# Main.net
KiCad netlist of a schematic drawn in Altium Designer
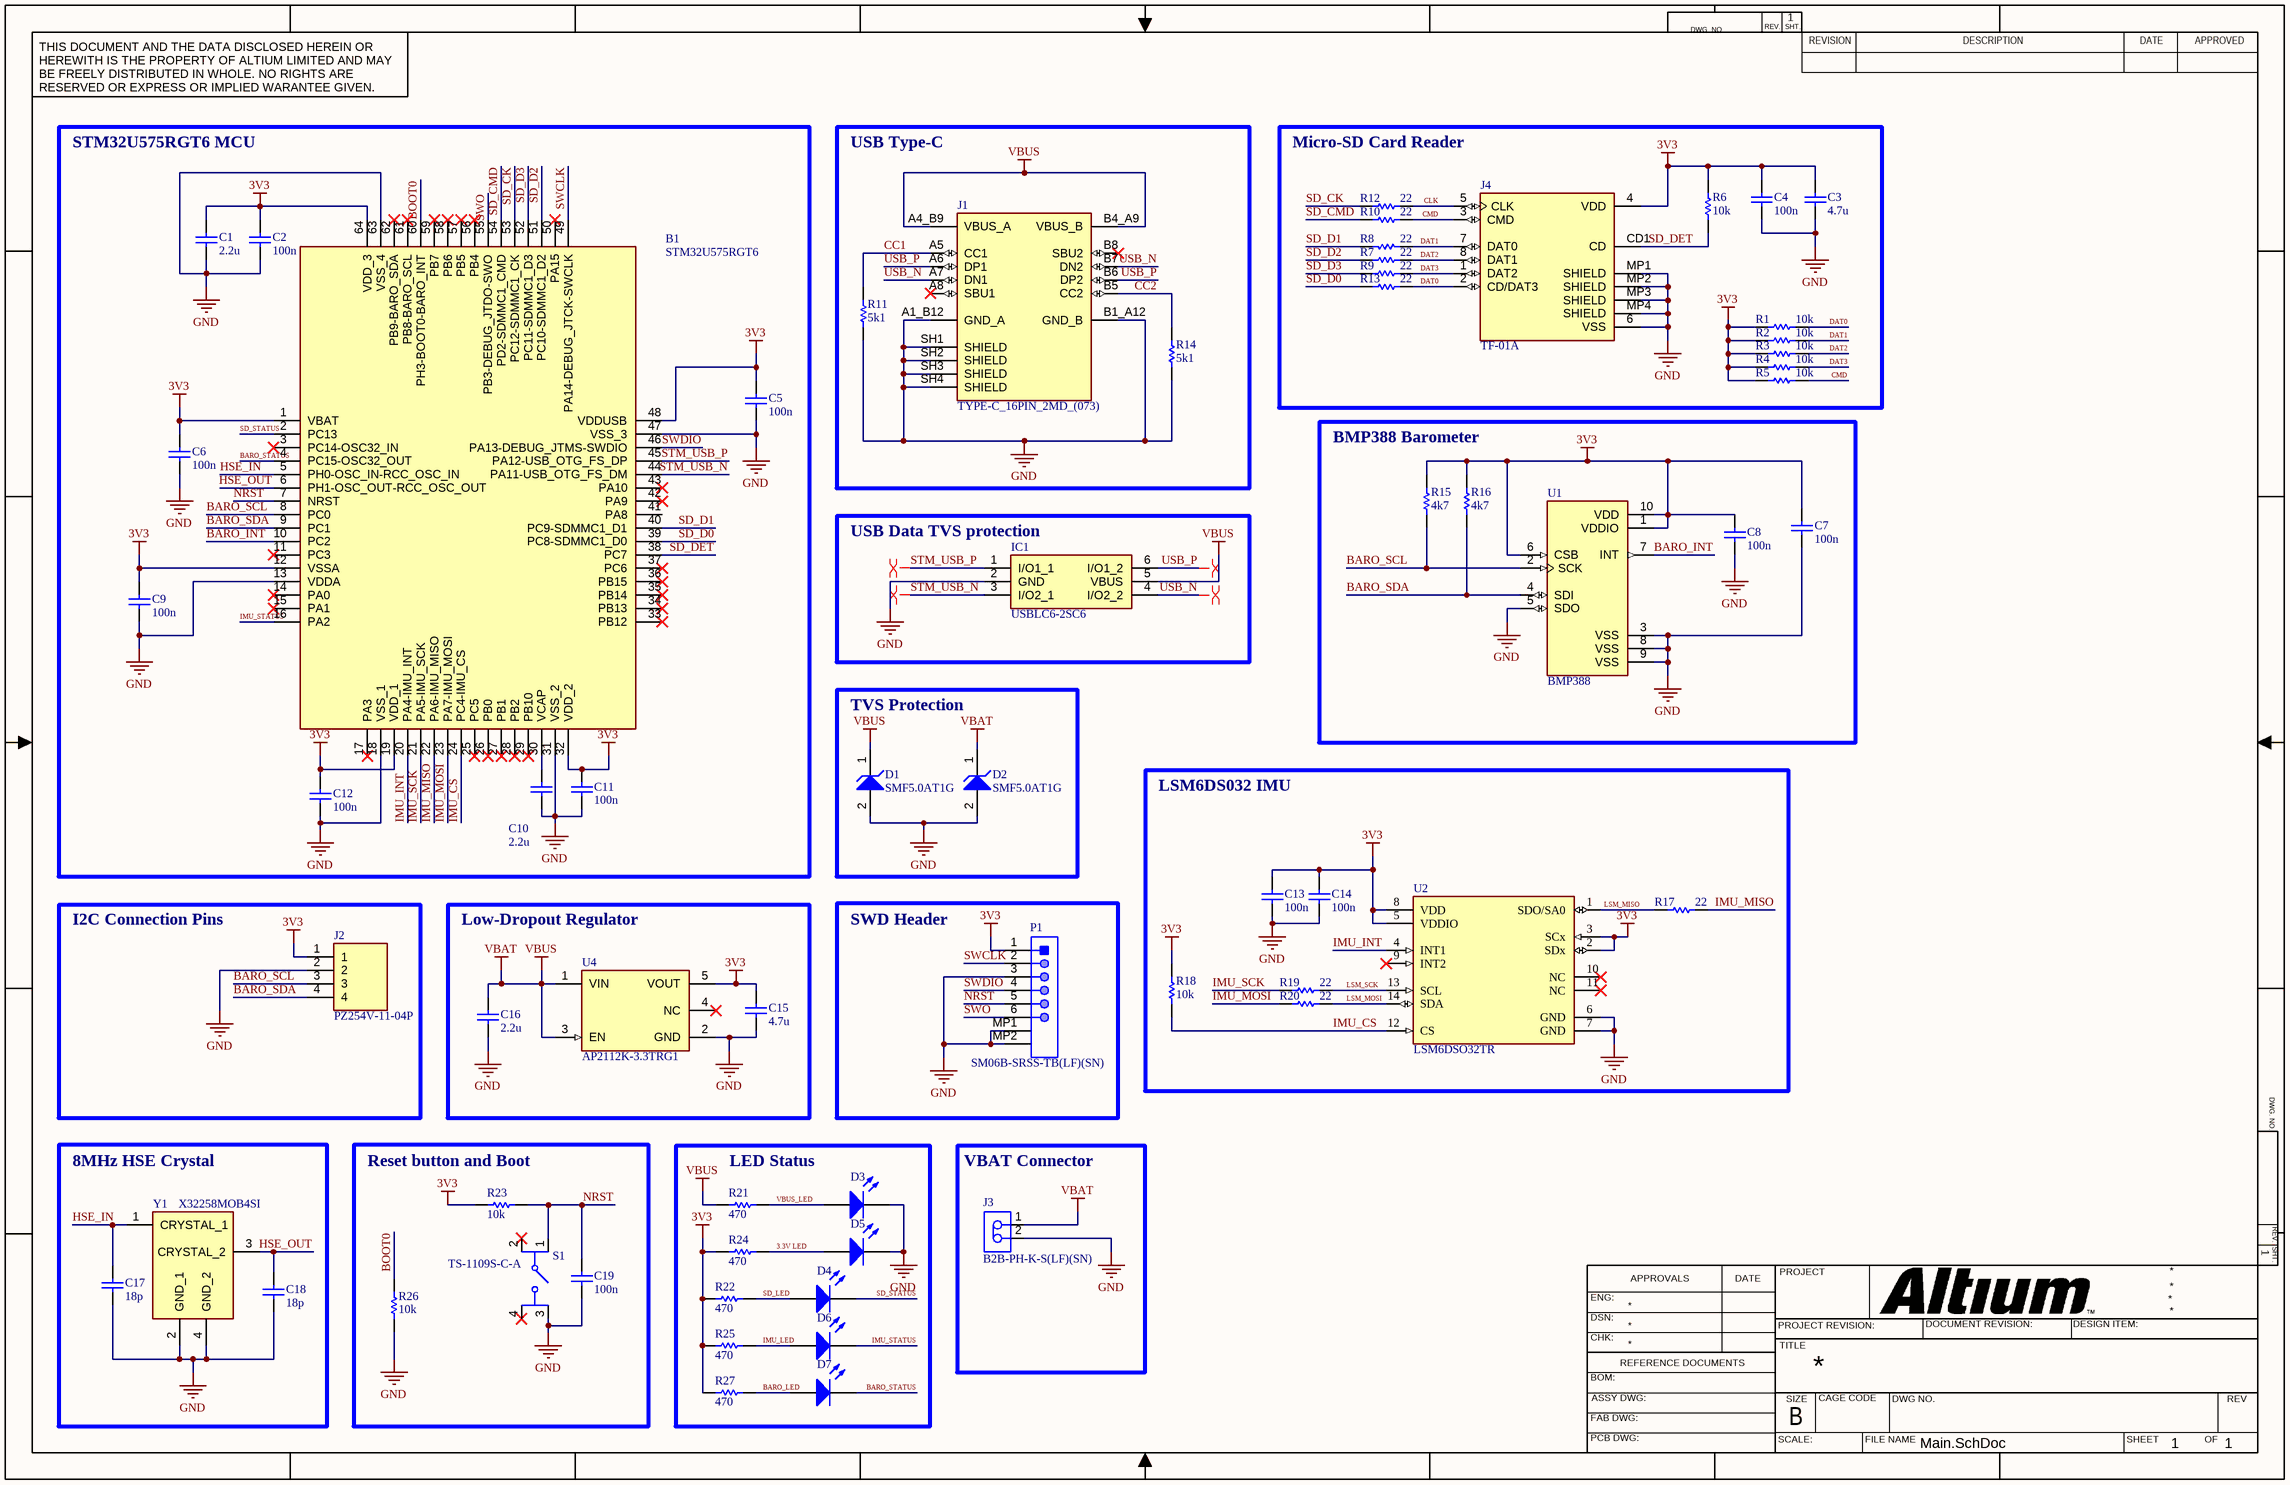
[diagram p0: Main.SchDoc]

(export (version "E")
  (design (tool "Eeschema 10.0.6"))
  (components
    (comp (ref "B1")
      (value "STM32U575RGT6")
      (footprint "SamacSys:QFP50P1200X1200X160-64N")
      (libsource (lib "SamacSys") (part "STM32U575RGT6"))
    )
    (comp (ref "C1")
      (value "2.2u")
      (footprint "CAPC1608X90X40LL10T20")
      (description "2.2u Capacitor 0603 CL10A225KO8NNNC")
      (fields (field (name "Comment") "Capacitor"))
      (libsource (lib "Simulation Generic Components") (part "Capacitor"))
    )
    (comp (ref "C2")
      (value "100n")
      (footprint "CAPC0402(1005)60_L")
      (description "100n Capacitor 0402 CL05B104KO5NNNC")
      (fields (field (name "Comment") "Capacitor"))
      (libsource (lib "Simulation Generic Components") (part "Capacitor"))
    )
    (comp (ref "C3")
      (value "4.7u")
      (footprint "CAPC1608X90X40LL10T20")
      (description "4.7u Capacitor 0603 CL10A475KO8NNNC")
      (fields (field (name "Comment") "Capacitor"))
      (libsource (lib "Simulation Generic Components") (part "Capacitor"))
    )
    (comp (ref "C4")
      (value "100n")
      (footprint "CAPC0402(1005)60_L")
      (description "100n Capacitor 0402 CL05B104KO5NNNC")
      (fields (field (name "Comment") "Capacitor"))
      (libsource (lib "Simulation Generic Components") (part "Capacitor"))
    )
    (comp (ref "C5")
      (value "100n")
      (footprint "CAPC0402(1005)60_L")
      (description "100n Capacitor 0402 CL05B104KO5NNNC")
      (fields (field (name "Comment") "Capacitor"))
      (libsource (lib "Simulation Generic Components") (part "Capacitor"))
    )
    (comp (ref "C6")
      (value "100n")
      (footprint "CAPC0402(1005)60_L")
      (description "100n Capacitor 0402 CL05B104KO5NNNC")
      (fields (field (name "Comment") "Capacitor"))
      (libsource (lib "Simulation Generic Components") (part "Capacitor"))
    )
    (comp (ref "C7")
      (value "100n")
      (footprint "CAPC0402(1005)60_L")
      (description "100n Capacitor 0402 CL05B104KO5NNNC")
      (fields (field (name "Comment") "Capacitor"))
      (libsource (lib "Simulation Generic Components") (part "Capacitor"))
    )
    (comp (ref "C8")
      (value "100n")
      (footprint "CAPC0402(1005)60_L")
      (description "100n Capacitor 0402 CL05B104KO5NNNC")
      (fields (field (name "Comment") "Capacitor"))
      (libsource (lib "Simulation Generic Components") (part "Capacitor"))
    )
    (comp (ref "C9")
      (value "100n")
      (footprint "CAPC0402(1005)60_L")
      (description "100n Capacitor 0402 CL05B104KO5NNNC")
      (fields (field (name "Comment") "Capacitor"))
      (libsource (lib "Simulation Generic Components") (part "Capacitor"))
    )
    (comp (ref "C10")
      (value "2.2u")
      (footprint "CAPC1608X90X40LL10T20")
      (description "2.2u Capacitor 0603 CL10A225KO8NNNC")
      (fields (field (name "Comment") "Capacitor"))
      (libsource (lib "Simulation Generic Components") (part "Capacitor"))
    )
    (comp (ref "C11")
      (value "100n")
      (footprint "CAPC0402(1005)60_L")
      (description "100n Capacitor 0402 CL05B104KO5NNNC")
      (fields (field (name "Comment") "Capacitor"))
      (libsource (lib "Simulation Generic Components") (part "Capacitor"))
    )
    (comp (ref "C12")
      (value "100n")
      (footprint "CAPC0402(1005)60_L")
      (description "100n Capacitor 0402 CL05B104KO5NNNC")
      (fields (field (name "Comment") "Capacitor"))
      (libsource (lib "Simulation Generic Components") (part "Capacitor"))
    )
    (comp (ref "C13")
      (value "100n")
      (footprint "CAPC0402(1005)60_L")
      (description "100n Capacitor 0402 CL05B104KO5NNNC")
      (fields (field (name "Comment") "Capacitor"))
      (libsource (lib "Simulation Generic Components") (part "Capacitor"))
    )
    (comp (ref "C14")
      (value "100n")
      (footprint "CAPC0402(1005)60_L")
      (description "100n Capacitor 0402 CL05B104KO5NNNC")
      (fields (field (name "Comment") "Capacitor"))
      (libsource (lib "Simulation Generic Components") (part "Capacitor"))
    )
    (comp (ref "C15")
      (value "4.7u")
      (footprint "CAPC1608X90X40LL10T20")
      (description "4.7u Capacitor 0603 CL10A475KO8NNNC")
      (fields (field (name "Comment") "Capacitor"))
      (libsource (lib "Simulation Generic Components") (part "Capacitor"))
    )
    (comp (ref "C16")
      (value "2.2u")
      (footprint "CAPC1608X90X40LL10T20")
      (description "2.2u Capacitor 0603 CL10A225KO8NNNC")
      (fields (field (name "Comment") "Capacitor"))
      (libsource (lib "Simulation Generic Components") (part "Capacitor"))
    )
    (comp (ref "C17")
      (value "18p")
      (footprint "CAPC0402(1005)60_L")
      (description "18p Capacitor 0402 0402CG180J500NT")
      (fields (field (name "Comment") "Capacitor"))
      (libsource (lib "Simulation Generic Components") (part "Capacitor"))
    )
    (comp (ref "C18")
      (value "18p")
      (footprint "CAPC0402(1005)60_L")
      (description "18p Capacitor 0402 0402CG180J500NT")
      (fields (field (name "Comment") "Capacitor"))
      (libsource (lib "Simulation Generic Components") (part "Capacitor"))
    )
    (comp (ref "C19")
      (value "100n")
      (footprint "CAPC0402(1005)60_L")
      (description "100n Capacitor 0402 CL05B104KO5NNNC")
      (fields (field (name "Comment") "Capacitor"))
      (libsource (lib "Simulation Generic Components") (part "Capacitor"))
    )
    (comp (ref "D1")
      (value "SMF5.0AT1G")
      (footprint "ONSC-SOD-123FL-2-498_V")
      (description "200 W Transient Voltage Suppressor, 2-Pin SOD-123FL, Pb-Free, Tape and Reel")
      (fields (field (name "MANUFACTURER") "On Semiconductor"))
      (libsource (lib "Altium Content Vault") (part "ONSC-K1A2-2"))
    )
    (comp (ref "D2")
      (value "SMF5.0AT1G")
      (footprint "ONSC-SOD-123FL-2-498_V")
      (description "200 W Transient Voltage Suppressor, 2-Pin SOD-123FL, Pb-Free, Tape and Reel")
      (fields (field (name "MANUFACTURER") "On Semiconductor"))
      (libsource (lib "Altium Content Vault") (part "ONSC-K1A2-2"))
    )
    (comp (ref "D3")
      (value "Light-Emitting Diode")
      (footprint "D0603:LTST-C191KRKT_V")
      (description "Red Light-Emitting Diode 0603 KT-0603R")
      (libsource (lib "Simulation Generic Components") (part "LED"))
    )
    (comp (ref "D4")
      (value "Light-Emitting Diode")
      (footprint "D0603:LTST-C191KRKT_V")
      (description "Red Light-Emitting Diode 0603 KT-0603R")
      (libsource (lib "Simulation Generic Components") (part "LED"))
    )
    (comp (ref "D5")
      (value "Light-Emitting Diode")
      (footprint "D0603:LTST-C191KRKT_V")
      (description "Red Light-Emitting Diode 0603 KT-0603R")
      (libsource (lib "Simulation Generic Components") (part "LED"))
    )
    (comp (ref "D6")
      (value "Light-Emitting Diode")
      (footprint "D0603:LTST-C191KRKT_V")
      (description "Red Light-Emitting Diode 0603 KT-0603R")
      (libsource (lib "Simulation Generic Components") (part "LED"))
    )
    (comp (ref "D7")
      (value "Light-Emitting Diode")
      (footprint "D0603:LTST-C191KRKT_V")
      (description "Red Light-Emitting Diode 0603 KT-0603R")
      (libsource (lib "Simulation Generic Components") (part "LED"))
    )
    (comp (ref "IC1")
      (value "USBLC6-2SC6")
      (footprint "SamacSys:SOT95P280X145-6N")
      (description "Integrated Circuit")
      (fields (field (name "MOUSER PART NUMBER") "511-USBLC6-2SC6"))
      (libsource (lib "SamacSys") (part "USBLC6-2SC6"))
    )
    (comp (ref "J1")
      (value "TYPE-C_16PIN_2MD_(073)")
      (footprint "SHOUHAN_TYPE-C_16PIN_2MD_(073)")
      (description "DC-5V 5A Type C USB")
      (fields (field (name "MP") "TYPE-C 16PIN 2MD (073)") (field (name "MF") "Shouhan"))
      (libsource (lib "Barney's Workspace") (part "TYPE-C_16PIN_2MD_(073)"))
    )
    (comp (ref "J2")
      (value "PZ254V-11-04P")
      (footprint "SamacSys:HDRV4W64P0X254_1X4_1016X250X890P")
      (description "Connector")
      (libsource (lib "SamacSys") (part "PZ254V-11-04P"))
    )
    (comp (ref "J3")
      (value "B2B-PH-K-S(LF)(SN)")
      (footprint "JST-B2B-PH-K-S_V")
      (fields (field (name "MANUFACTURER") "JST"))
      (libsource (lib "Altium Content Vault") (part "CN-2P-F-QF2"))
    )
    (comp (ref "J4")
      (value "TF-01A")
      (footprint "TF-01A")
      (description "Standard Card Edge Connectors")
      (fields (field (name "MF") "HRO Electronics Co., Ltd."))
      (libsource (lib "Barney's Workspace") (part "TF-01A"))
    )
    (comp (ref "P1")
      (value "SM06B-SRSS-TB(LF)(SN)")
      (footprint "JST-SM06B-SRSS-TB_V")
      (description "Male Header, Pitch 1 mm, 1 x 6 Position, Height 2.95 mm, -25 to 85 degC, RoHS, Tape and Reel")
      (fields (field (name "MANUFACTURER") "JST"))
      (libsource (lib "Altium Content Vault") (part "CN-1P-2M-R6"))
    )
    (comp (ref "R1")
      (value "10k")
      (footprint "RESC0402(1005)_L")
      (description "10k Resistor 0402 0402WGF1002TCE")
      (fields (field (name "Comment") "Resistor"))
      (libsource (lib "Simulation Generic Components") (part "Resistor"))
    )
    (comp (ref "R2")
      (value "10k")
      (footprint "RESC0402(1005)_L")
      (description "10k Resistor 0402 0402WGF1002TCE")
      (fields (field (name "Comment") "Resistor"))
      (libsource (lib "Simulation Generic Components") (part "Resistor"))
    )
    (comp (ref "R3")
      (value "10k")
      (footprint "RESC0402(1005)_L")
      (description "10k Resistor 0402 0402WGF1002TCE")
      (fields (field (name "Comment") "Resistor"))
      (libsource (lib "Simulation Generic Components") (part "Resistor"))
    )
    (comp (ref "R4")
      (value "10k")
      (footprint "RESC0402(1005)_L")
      (description "10k Resistor 0402 0402WGF1002TCE")
      (fields (field (name "Comment") "Resistor"))
      (libsource (lib "Simulation Generic Components") (part "Resistor"))
    )
    (comp (ref "R5")
      (value "10k")
      (footprint "RESC0402(1005)_L")
      (description "10k Resistor 0402 0402WGF1002TCE")
      (fields (field (name "Comment") "Resistor"))
      (libsource (lib "Simulation Generic Components") (part "Resistor"))
    )
    (comp (ref "R6")
      (value "10k")
      (footprint "RESC0402(1005)_L")
      (description "10k Resistor 0402 0402WGF1002TCE")
      (fields (field (name "Comment") "Resistor"))
      (libsource (lib "Simulation Generic Components") (part "Resistor"))
    )
    (comp (ref "R7")
      (value "22")
      (footprint "RESC0402(1005)_L")
      (description "22 Resistor 0402 0402WGF220JTCE")
      (fields (field (name "Comment") "Resistor"))
      (libsource (lib "Simulation Generic Components") (part "Resistor"))
    )
    (comp (ref "R8")
      (value "22")
      (footprint "RESC0402(1005)_L")
      (description "22 Resistor 0402 0402WGF220JTCE")
      (fields (field (name "Comment") "Resistor"))
      (libsource (lib "Simulation Generic Components") (part "Resistor"))
    )
    (comp (ref "R9")
      (value "22")
      (footprint "RESC0402(1005)_L")
      (description "22 Resistor 0402 0402WGF220JTCE")
      (fields (field (name "Comment") "Resistor"))
      (libsource (lib "Simulation Generic Components") (part "Resistor"))
    )
    (comp (ref "R10")
      (value "22")
      (footprint "RESC0402(1005)_L")
      (description "22 Resistor 0402 0402WGF220JTCE")
      (fields (field (name "Comment") "Resistor"))
      (libsource (lib "Simulation Generic Components") (part "Resistor"))
    )
    (comp (ref "R11")
      (value "5k1")
      (footprint "RESC0402(1005)_L")
      (description "5k1 Resistor 0402 0402WGF5101TCE")
      (fields (field (name "Comment") "Resistor"))
      (libsource (lib "Simulation Generic Components") (part "Resistor"))
    )
    (comp (ref "R12")
      (value "22")
      (footprint "RESC0402(1005)_L")
      (description "22 Resistor 0402 0402WGF220JTCE")
      (fields (field (name "Comment") "Resistor"))
      (libsource (lib "Simulation Generic Components") (part "Resistor"))
    )
    (comp (ref "R13")
      (value "22")
      (footprint "RESC0402(1005)_L")
      (description "22 Resistor 0402 0402WGF220JTCE")
      (fields (field (name "Comment") "Resistor"))
      (libsource (lib "Simulation Generic Components") (part "Resistor"))
    )
    (comp (ref "R14")
      (value "5k1")
      (footprint "RESC0402(1005)_L")
      (description "5k1 Resistor 0402 0402WGF5101TCE")
      (fields (field (name "Comment") "Resistor"))
      (libsource (lib "Simulation Generic Components") (part "Resistor"))
    )
    (comp (ref "R15")
      (value "4k7")
      (footprint "RESC0402(1005)_L")
      (description "4k7 Resistor 0402 0402WGF4701TCE")
      (fields (field (name "Comment") "Resistor"))
      (libsource (lib "Simulation Generic Components") (part "Resistor"))
    )
    (comp (ref "R16")
      (value "4k7")
      (footprint "RESC0402(1005)_L")
      (description "4k7 Resistor 0402 0402WGF4701TCE")
      (fields (field (name "Comment") "Resistor"))
      (libsource (lib "Simulation Generic Components") (part "Resistor"))
    )
    (comp (ref "R17")
      (value "22")
      (footprint "RESC0402(1005)_L")
      (description "22 Resistor 0402 0402WGF220JTCE")
      (fields (field (name "Comment") "Resistor"))
      (libsource (lib "Simulation Generic Components") (part "Resistor"))
    )
    (comp (ref "R18")
      (value "10k")
      (footprint "RESC0402(1005)_L")
      (description "10k Resistor 0402 0402WGF1002TCE")
      (fields (field (name "Comment") "Resistor"))
      (libsource (lib "Simulation Generic Components") (part "Resistor"))
    )
    (comp (ref "R19")
      (value "22")
      (footprint "RESC0402(1005)_L")
      (description "22 Resistor 0402 0402WGF220JTCE")
      (fields (field (name "Comment") "Resistor"))
      (libsource (lib "Simulation Generic Components") (part "Resistor"))
    )
    (comp (ref "R20")
      (value "22")
      (footprint "RESC0402(1005)_L")
      (description "22 Resistor 0402 0402WGF220JTCE")
      (fields (field (name "Comment") "Resistor"))
      (libsource (lib "Simulation Generic Components") (part "Resistor"))
    )
    (comp (ref "R21")
      (value "470")
      (footprint "R0603:RESC1608X55X25LL10T15")
      (description "470 Resistor 0603 0603WAF4700T5E")
      (fields (field (name "Comment") "Resistor"))
      (libsource (lib "Simulation Generic Components") (part "Resistor"))
    )
    (comp (ref "R22")
      (value "470")
      (footprint "R0603:RESC1608X55X25LL10T15")
      (description "470 Resistor 0603 0603WAF4700T5E")
      (fields (field (name "Comment") "Resistor"))
      (libsource (lib "Simulation Generic Components") (part "Resistor"))
    )
    (comp (ref "R23")
      (value "10k")
      (footprint "RESC0402(1005)_L")
      (description "10k Resistor 0402 0402WGF1002TCE")
      (fields (field (name "Comment") "Resistor"))
      (libsource (lib "Simulation Generic Components") (part "Resistor"))
    )
    (comp (ref "R24")
      (value "470")
      (footprint "R0603:RESC1608X55X25LL10T15")
      (description "470 Resistor 0603 0603WAF4700T5E")
      (fields (field (name "Comment") "Resistor"))
      (libsource (lib "Simulation Generic Components") (part "Resistor"))
    )
    (comp (ref "R25")
      (value "470")
      (footprint "R0603:RESC1608X55X25LL10T15")
      (description "470 Resistor 0603 0603WAF4700T5E")
      (fields (field (name "Comment") "Resistor"))
      (libsource (lib "Simulation Generic Components") (part "Resistor"))
    )
    (comp (ref "R26")
      (value "10k")
      (footprint "RESC0402(1005)_L")
      (description "10k Resistor 0402 0402WGF1002TCE")
      (fields (field (name "Comment") "Resistor"))
      (libsource (lib "Simulation Generic Components") (part "Resistor"))
    )
    (comp (ref "R27")
      (value "470")
      (footprint "R0603:RESC1608X55X25LL10T15")
      (description "470 Resistor 0603 0603WAF4700T5E")
      (fields (field (name "Comment") "Resistor"))
      (libsource (lib "Simulation Generic Components") (part "Resistor"))
    )
    (comp (ref "S1")
      (value "TS-1109S-C-A")
      (footprint "SamacSys:TS1109SCA")
      (description "Switch (4-Pin Push)")
      (libsource (lib "*") (part "TS-1109S-C-A"))
    )
    (comp (ref "U1")
      (value "BMP388")
      (footprint "PQFN50P200X200X80-10N")
      (description "P-Sensor SPI I2C 1, 25 Bar SMD")
      (libsource (lib "Barney's Workspace") (part "BMP388"))
    )
    (comp (ref "U2")
      (value "LSM6DSO32TR")
      (footprint "FP-LGA-14L-DM00249496-MFG")
      (description "INEMO INERTIAL MODULE: 3D ACCELE")
      (libsource (lib "Altium Content Vault") (part "593856c316c551aebc7657d93cdb4f0"))
    )
    (comp (ref "U4")
      (value "AP2112K-3.3TRG1")
      (footprint "FP-SOT25-IPC_C")
      (description "IC REG LINEAR 3.3V 600MA SOT25")
      (libsource (lib "Altium Content Vault") (part "c8ab751aee5229183125ab046a11caa"))
    )
    (comp (ref "Y1")
      (value "X32258MOB4SI")
      (footprint "SamacSys:X32258MOB4SI")
      (description "Crystal or Oscillator")
      (libsource (lib "SamacSys") (part "X32258MOB4SI"))
    )
  )
  (nets
    (net (code "1") (name "/3.3V LED") (class "Default")
      (node (ref "D5") (pin "1") (pinfunction "A_1") (pintype "passive"))
      (node (ref "R24") (pin "2") (pinfunction "2_2") (pintype "passive"))
    )
    (net (code "2") (name "/BARO_INT") (class "Default")
      (node (ref "B1") (pin "10") (pinfunction "PC2_10") (pintype "passive"))
      (node (ref "U1") (pin "7") (pinfunction "INT_7") (pintype "output"))
    )
    (net (code "3") (name "/BARO_LED") (class "Default")
      (node (ref "D7") (pin "1") (pinfunction "A_1") (pintype "passive"))
      (node (ref "R27") (pin "2") (pinfunction "2_2") (pintype "passive"))
    )
    (net (code "4") (name "/BARO_SCL") (class "Default")
      (node (ref "B1") (pin "8") (pinfunction "PC0_8") (pintype "passive"))
      (node (ref "J2") (pin "3") (pinfunction "3_3") (pintype "passive"))
      (node (ref "R15") (pin "1") (pinfunction "1_1") (pintype "passive"))
      (node (ref "U1") (pin "2") (pinfunction "SCK_2") (pintype "input"))
    )
    (net (code "5") (name "/BARO_SDA") (class "Default")
      (node (ref "B1") (pin "9") (pinfunction "PC1_9") (pintype "passive"))
      (node (ref "J2") (pin "4") (pinfunction "4_4") (pintype "passive"))
      (node (ref "R16") (pin "1") (pinfunction "1_1") (pintype "passive"))
      (node (ref "U1") (pin "4") (pinfunction "SDI_4") (pintype "bidirectional"))
    )
    (net (code "6") (name "/BARO_STATUS") (class "Default")
      (node (ref "B1") (pin "4") (pinfunction "PC15-OSC32_OUT_4") (pintype "passive"))
      (node (ref "D7") (pin "2") (pinfunction "K_2") (pintype "passive"))
    )
    (net (code "7") (name "/BOOT0") (class "Default")
      (node (ref "B1") (pin "60") (pinfunction "PH3-BOOT0-BARO_INT_60") (pintype "passive"))
      (node (ref "R26") (pin "2") (pinfunction "2_2") (pintype "passive"))
    )
    (net (code "8") (name "/CC1") (class "Default")
      (node (ref "J1") (pin "A5") (pinfunction "CC1_A5") (pintype "bidirectional"))
      (node (ref "R11") (pin "2") (pinfunction "2_2") (pintype "passive"))
    )
    (net (code "9") (name "/CC2") (class "Default")
      (node (ref "J1") (pin "B5") (pinfunction "CC2_B5") (pintype "bidirectional"))
      (node (ref "R14") (pin "2") (pinfunction "2_2") (pintype "passive"))
    )
    (net (code "10") (name "/CLK") (class "Default")
      (node (ref "J4") (pin "5") (pinfunction "CLK_5") (pintype "bidirectional"))
      (node (ref "R12") (pin "1") (pinfunction "1_1") (pintype "passive"))
    )
    (net (code "11") (name "/CMD") (class "Default")
      (node (ref "J4") (pin "3") (pinfunction "CMD_3") (pintype "bidirectional"))
      (node (ref "R10") (pin "1") (pinfunction "1_1") (pintype "passive"))
      (node (ref "R5") (pin "2") (pinfunction "2_2") (pintype "passive"))
    )
    (net (code "12") (name "/DAT0") (class "Default")
      (node (ref "J4") (pin "2") (pinfunction "CD/DAT3_2") (pintype "bidirectional"))
      (node (ref "R1") (pin "2") (pinfunction "2_2") (pintype "passive"))
      (node (ref "R13") (pin "1") (pinfunction "1_1") (pintype "passive"))
    )
    (net (code "13") (name "/DAT1") (class "Default")
      (node (ref "J4") (pin "7") (pinfunction "DAT0_7") (pintype "bidirectional"))
      (node (ref "R2") (pin "2") (pinfunction "2_2") (pintype "passive"))
      (node (ref "R8") (pin "2") (pinfunction "2_2") (pintype "passive"))
    )
    (net (code "14") (name "/DAT2") (class "Default")
      (node (ref "J4") (pin "8") (pinfunction "DAT1_8") (pintype "bidirectional"))
      (node (ref "R3") (pin "2") (pinfunction "2_2") (pintype "passive"))
      (node (ref "R7") (pin "1") (pinfunction "1_1") (pintype "passive"))
    )
    (net (code "15") (name "/DAT3") (class "Default")
      (node (ref "J4") (pin "1") (pinfunction "DAT2_1") (pintype "bidirectional"))
      (node (ref "R4") (pin "2") (pinfunction "2_2") (pintype "passive"))
      (node (ref "R9") (pin "1") (pinfunction "1_1") (pintype "passive"))
    )
    (net (code "16") (name "/HSE_IN") (class "Default")
      (node (ref "B1") (pin "5") (pinfunction "PH0-OSC_IN-RCC_OSC_IN_5") (pintype "passive"))
      (node (ref "C17") (pin "2") (pinfunction "2_2") (pintype "passive"))
      (node (ref "Y1") (pin "1") (pinfunction "CRYSTAL_1_1") (pintype "passive"))
    )
    (net (code "17") (name "/HSE_OUT") (class "Default")
      (node (ref "B1") (pin "6") (pinfunction "PH1-OSC_OUT-RCC_OSC_OUT_6") (pintype "passive"))
      (node (ref "C18") (pin "2") (pinfunction "2_2") (pintype "passive"))
      (node (ref "Y1") (pin "3") (pinfunction "CRYSTAL_2_3") (pintype "passive"))
    )
    (net (code "18") (name "/IMU_CS") (class "Default")
      (node (ref "B1") (pin "24") (pinfunction "PC4-IMU_CS_24") (pintype "passive"))
      (node (ref "R18") (pin "1") (pinfunction "1_1") (pintype "passive"))
      (node (ref "U2") (pin "12") (pinfunction "CS_12") (pintype "input"))
    )
    (net (code "19") (name "/IMU_INT") (class "Default")
      (node (ref "B1") (pin "20") (pinfunction "PA4-IMU_INT_20") (pintype "passive"))
      (node (ref "U2") (pin "4") (pinfunction "INT1_4") (pintype "input"))
    )
    (net (code "20") (name "/IMU_LED") (class "Default")
      (node (ref "D6") (pin "1") (pinfunction "A_1") (pintype "passive"))
      (node (ref "R25") (pin "2") (pinfunction "2_2") (pintype "passive"))
    )
    (net (code "21") (name "/IMU_MISO") (class "Default")
      (node (ref "B1") (pin "22") (pinfunction "PA6-IMU_MISO_22") (pintype "passive"))
      (node (ref "R17") (pin "1") (pinfunction "1_1") (pintype "passive"))
    )
    (net (code "22") (name "/IMU_MOSI") (class "Default")
      (node (ref "B1") (pin "23") (pinfunction "PA7-IMU_MOSI_23") (pintype "passive"))
      (node (ref "R20") (pin "2") (pinfunction "2_2") (pintype "passive"))
    )
    (net (code "23") (name "/IMU_SCK") (class "Default")
      (node (ref "B1") (pin "21") (pinfunction "PA5-IMU_SCK_21") (pintype "passive"))
      (node (ref "R19") (pin "2") (pinfunction "2_2") (pintype "passive"))
    )
    (net (code "24") (name "/IMU_STATUS") (class "Default")
      (node (ref "B1") (pin "16") (pinfunction "PA2_16") (pintype "passive"))
      (node (ref "D6") (pin "2") (pinfunction "K_2") (pintype "passive"))
    )
    (net (code "25") (name "/LSM_MISO") (class "Default")
      (node (ref "R17") (pin "2") (pinfunction "2_2") (pintype "passive"))
      (node (ref "U2") (pin "1") (pinfunction "SDO/SA0_1") (pintype "bidirectional"))
    )
    (net (code "26") (name "/LSM_MOSI") (class "Default")
      (node (ref "R20") (pin "1") (pinfunction "1_1") (pintype "passive"))
      (node (ref "U2") (pin "14") (pinfunction "SDA_14") (pintype "bidirectional"))
    )
    (net (code "27") (name "/LSM_SCK") (class "Default")
      (node (ref "R19") (pin "1") (pinfunction "1_1") (pintype "passive"))
      (node (ref "U2") (pin "13") (pinfunction "SCL_13") (pintype "input"))
    )
    (net (code "28") (name "/NRST") (class "Default")
      (node (ref "B1") (pin "7") (pinfunction "NRST_7") (pintype "passive"))
      (node (ref "C19") (pin "2") (pinfunction "2_2") (pintype "passive"))
      (node (ref "P1") (pin "5") (pinfunction "5_5") (pintype "passive"))
      (node (ref "R23") (pin "1") (pinfunction "1_1") (pintype "passive"))
      (node (ref "S1") (pin "1") (pinfunction "COM_1_1") (pintype "passive"))
    )
    (net (code "29") (name "/SD_CK") (class "Default")
      (node (ref "B1") (pin "53") (pinfunction "PC12-SDMMC1_CK_53") (pintype "passive"))
      (node (ref "R12") (pin "2") (pinfunction "2_2") (pintype "passive"))
    )
    (net (code "30") (name "/SD_CMD") (class "Default")
      (node (ref "B1") (pin "54") (pinfunction "PD2-SDMMC1_CMD_54") (pintype "passive"))
      (node (ref "R10") (pin "2") (pinfunction "2_2") (pintype "passive"))
    )
    (net (code "31") (name "/SD_D0") (class "Default")
      (node (ref "B1") (pin "39") (pinfunction "PC8-SDMMC1_D0_39") (pintype "passive"))
      (node (ref "R13") (pin "2") (pinfunction "2_2") (pintype "passive"))
    )
    (net (code "32") (name "/SD_D1") (class "Default")
      (node (ref "B1") (pin "40") (pinfunction "PC9-SDMMC1_D1_40") (pintype "passive"))
      (node (ref "R8") (pin "1") (pinfunction "1_1") (pintype "passive"))
    )
    (net (code "33") (name "/SD_D2") (class "Default")
      (node (ref "B1") (pin "51") (pinfunction "PC10-SDMMC1_D2_51") (pintype "passive"))
      (node (ref "R7") (pin "2") (pinfunction "2_2") (pintype "passive"))
    )
    (net (code "34") (name "/SD_D3") (class "Default")
      (node (ref "B1") (pin "52") (pinfunction "PC11-SDMMC1_D3_52") (pintype "passive"))
      (node (ref "R9") (pin "2") (pinfunction "2_2") (pintype "passive"))
    )
    (net (code "35") (name "/SD_DET") (class "Default")
      (node (ref "B1") (pin "38") (pinfunction "PC7_38") (pintype "passive"))
      (node (ref "J4") (pin "CD1") (pinfunction "CD_CD1") (pintype "passive"))
      (node (ref "R6") (pin "1") (pinfunction "1_1") (pintype "passive"))
    )
    (net (code "36") (name "/SD_LED") (class "Default")
      (node (ref "D4") (pin "1") (pinfunction "A_1") (pintype "passive"))
      (node (ref "R22") (pin "2") (pinfunction "2_2") (pintype "passive"))
    )
    (net (code "37") (name "/SD_STATUS") (class "Default")
      (node (ref "B1") (pin "2") (pinfunction "PC13_2") (pintype "passive"))
      (node (ref "D4") (pin "2") (pinfunction "K_2") (pintype "passive"))
    )
    (net (code "38") (name "/STM_USB_N") (class "Default")
      (node (ref "B1") (pin "44") (pinfunction "PA11-USB_OTG_FS_DM_44") (pintype "passive"))
      (node (ref "IC1") (pin "3") (pinfunction "I/O2_1_3") (pintype "passive"))
    )
    (net (code "39") (name "/STM_USB_P") (class "Default")
      (node (ref "B1") (pin "45") (pinfunction "PA12-USB_OTG_FS_DP_45") (pintype "passive"))
      (node (ref "IC1") (pin "1") (pinfunction "I/O1_1_1") (pintype "passive"))
    )
    (net (code "40") (name "/SWCLK") (class "Default")
      (node (ref "B1") (pin "49") (pinfunction "PA14-DEBUG_JTCK-SWCLK_49") (pintype "passive"))
      (node (ref "P1") (pin "2") (pinfunction "2_2") (pintype "passive"))
    )
    (net (code "41") (name "/SWDIO") (class "Default")
      (node (ref "B1") (pin "46") (pinfunction "PA13-DEBUG_JTMS-SWDIO_46") (pintype "passive"))
      (node (ref "P1") (pin "4") (pinfunction "4_4") (pintype "passive"))
    )
    (net (code "42") (name "/SWO") (class "Default")
      (node (ref "B1") (pin "55") (pinfunction "PB3-DEBUG_JTDO-SWO_55") (pintype "passive"))
      (node (ref "P1") (pin "6") (pinfunction "6_6") (pintype "passive"))
    )
    (net (code "43") (name "/USB_N") (class "Default")
      (node (ref "IC1") (pin "4") (pinfunction "I/O2_2_4") (pintype "passive"))
      (node (ref "J1") (pin "A7") (pinfunction "DN1_A7") (pintype "bidirectional"))
      (node (ref "J1") (pin "B7") (pinfunction "DN2_B7") (pintype "bidirectional"))
    )
    (net (code "44") (name "/USB_P") (class "Default")
      (node (ref "IC1") (pin "6") (pinfunction "I/O1_2_6") (pintype "passive"))
      (node (ref "J1") (pin "A6") (pinfunction "DP1_A6") (pintype "bidirectional"))
      (node (ref "J1") (pin "B6") (pinfunction "DP2_B6") (pintype "bidirectional"))
    )
    (net (code "45") (name "/VBUS_LED") (class "Default")
      (node (ref "D3") (pin "1") (pinfunction "A_1") (pintype "passive"))
      (node (ref "R21") (pin "2") (pinfunction "2_2") (pintype "passive"))
    )
    (net (code "46") (name "3V3") (class "Default")
      (node (ref "B1") (pin "1") (pinfunction "VBAT_1") (pintype "passive"))
      (node (ref "B1") (pin "12") (pinfunction "VSSA_12") (pintype "passive"))
      (node (ref "B1") (pin "19") (pinfunction "VDD_1_19") (pintype "passive"))
      (node (ref "B1") (pin "32") (pinfunction "VDD_2_32") (pintype "passive"))
      (node (ref "B1") (pin "48") (pinfunction "VDDUSB_48") (pintype "passive"))
      (node (ref "B1") (pin "64") (pinfunction "VDD_3_64") (pintype "passive"))
      (node (ref "C1") (pin "2") (pinfunction "2_2") (pintype "passive"))
      (node (ref "C11") (pin "2") (pinfunction "2_2") (pintype "passive"))
      (node (ref "C12") (pin "2") (pinfunction "2_2") (pintype "passive"))
      (node (ref "C13") (pin "2") (pinfunction "2_2") (pintype "passive"))
      (node (ref "C14") (pin "2") (pinfunction "2_2") (pintype "passive"))
      (node (ref "C15") (pin "2") (pinfunction "2_2") (pintype "passive"))
      (node (ref "C2") (pin "2") (pinfunction "2_2") (pintype "passive"))
      (node (ref "C3") (pin "2") (pinfunction "2_2") (pintype "passive"))
      (node (ref "C4") (pin "2") (pinfunction "2_2") (pintype "passive"))
      (node (ref "C5") (pin "2") (pinfunction "2_2") (pintype "passive"))
      (node (ref "C6") (pin "2") (pinfunction "2_2") (pintype "passive"))
      (node (ref "C7") (pin "2") (pinfunction "2_2") (pintype "passive"))
      (node (ref "C8") (pin "2") (pinfunction "2_2") (pintype "passive"))
      (node (ref "C9") (pin "2") (pinfunction "2_2") (pintype "passive"))
      (node (ref "J2") (pin "1") (pinfunction "1_1") (pintype "passive"))
      (node (ref "J4") (pin "4") (pinfunction "VDD_4") (pintype "power_in"))
      (node (ref "P1") (pin "1") (pinfunction "1_1") (pintype "passive"))
      (node (ref "R1") (pin "1") (pinfunction "1_1") (pintype "passive"))
      (node (ref "R15") (pin "2") (pinfunction "2_2") (pintype "passive"))
      (node (ref "R16") (pin "2") (pinfunction "2_2") (pintype "passive"))
      (node (ref "R18") (pin "2") (pinfunction "2_2") (pintype "passive"))
      (node (ref "R2") (pin "1") (pinfunction "1_1") (pintype "passive"))
      (node (ref "R22") (pin "1") (pinfunction "1_1") (pintype "passive"))
      (node (ref "R23") (pin "2") (pinfunction "2_2") (pintype "passive"))
      (node (ref "R24") (pin "1") (pinfunction "1_1") (pintype "passive"))
      (node (ref "R25") (pin "1") (pinfunction "1_1") (pintype "passive"))
      (node (ref "R27") (pin "1") (pinfunction "1_1") (pintype "passive"))
      (node (ref "R3") (pin "1") (pinfunction "1_1") (pintype "passive"))
      (node (ref "R4") (pin "1") (pinfunction "1_1") (pintype "passive"))
      (node (ref "R5") (pin "1") (pinfunction "1_1") (pintype "passive"))
      (node (ref "R6") (pin "2") (pinfunction "2_2") (pintype "passive"))
      (node (ref "U1") (pin "1") (pinfunction "VDDIO_1") (pintype "power_in"))
      (node (ref "U1") (pin "10") (pinfunction "VDD_10") (pintype "power_in"))
      (node (ref "U1") (pin "6") (pinfunction "CSB_6") (pintype "input"))
      (node (ref "U2") (pin "2") (pinfunction "SDx_2") (pintype "bidirectional"))
      (node (ref "U2") (pin "3") (pinfunction "SCx_3") (pintype "input"))
      (node (ref "U2") (pin "5") (pinfunction "VDDIO_5") (pintype "power_in"))
      (node (ref "U2") (pin "8") (pinfunction "VDD_8") (pintype "power_in"))
      (node (ref "U4") (pin "5") (pinfunction "VOUT_5") (pintype "power_in"))
    )
    (net (code "47") (name "GND") (class "Default")
      (node (ref "B1") (pin "13") (pinfunction "VDDA_13") (pintype "passive"))
      (node (ref "B1") (pin "18") (pinfunction "VSS_1_18") (pintype "passive"))
      (node (ref "B1") (pin "31") (pinfunction "VSS_2_31") (pintype "passive"))
      (node (ref "B1") (pin "47") (pinfunction "VSS_3_47") (pintype "passive"))
      (node (ref "B1") (pin "63") (pinfunction "VSS_4_63") (pintype "passive"))
      (node (ref "C1") (pin "1") (pinfunction "1_1") (pintype "passive"))
      (node (ref "C10") (pin "1") (pinfunction "1_1") (pintype "passive"))
      (node (ref "C11") (pin "1") (pinfunction "1_1") (pintype "passive"))
      (node (ref "C12") (pin "1") (pinfunction "1_1") (pintype "passive"))
      (node (ref "C13") (pin "1") (pinfunction "1_1") (pintype "passive"))
      (node (ref "C14") (pin "1") (pinfunction "1_1") (pintype "passive"))
      (node (ref "C15") (pin "1") (pinfunction "1_1") (pintype "passive"))
      (node (ref "C16") (pin "1") (pinfunction "1_1") (pintype "passive"))
      (node (ref "C17") (pin "1") (pinfunction "1_1") (pintype "passive"))
      (node (ref "C18") (pin "1") (pinfunction "1_1") (pintype "passive"))
      (node (ref "C19") (pin "1") (pinfunction "1_1") (pintype "passive"))
      (node (ref "C2") (pin "1") (pinfunction "1_1") (pintype "passive"))
      (node (ref "C3") (pin "1") (pinfunction "1_1") (pintype "passive"))
      (node (ref "C4") (pin "1") (pinfunction "1_1") (pintype "passive"))
      (node (ref "C5") (pin "1") (pinfunction "1_1") (pintype "passive"))
      (node (ref "C6") (pin "1") (pinfunction "1_1") (pintype "passive"))
      (node (ref "C7") (pin "1") (pinfunction "1_1") (pintype "passive"))
      (node (ref "C8") (pin "1") (pinfunction "1_1") (pintype "passive"))
      (node (ref "C9") (pin "1") (pinfunction "1_1") (pintype "passive"))
      (node (ref "D1") (pin "2") (pinfunction "A_2") (pintype "passive"))
      (node (ref "D2") (pin "2") (pinfunction "A_2") (pintype "passive"))
      (node (ref "D3") (pin "2") (pinfunction "K_2") (pintype "passive"))
      (node (ref "D5") (pin "2") (pinfunction "K_2") (pintype "passive"))
      (node (ref "IC1") (pin "2") (pinfunction "GND_2") (pintype "passive"))
      (node (ref "J1") (pin "A1_B12") (pinfunction "GND_A_A1_B12") (pintype "power_in"))
      (node (ref "J1") (pin "B1_A12") (pinfunction "GND_B_B1_A12") (pintype "power_in"))
      (node (ref "J1") (pin "SH1") (pinfunction "SHIELD_SH1") (pintype "passive"))
      (node (ref "J1") (pin "SH2") (pinfunction "SHIELD_SH2") (pintype "passive"))
      (node (ref "J1") (pin "SH3") (pinfunction "SHIELD_SH3") (pintype "passive"))
      (node (ref "J1") (pin "SH4") (pinfunction "SHIELD_SH4") (pintype "passive"))
      (node (ref "J2") (pin "2") (pinfunction "2_2") (pintype "passive"))
      (node (ref "J3") (pin "2") (pinfunction "2_2") (pintype "passive"))
      (node (ref "J4") (pin "6") (pinfunction "VSS_6") (pintype "power_in"))
      (node (ref "J4") (pin "MP1") (pinfunction "SHIELD_MP1") (pintype "power_in"))
      (node (ref "J4") (pin "MP2") (pinfunction "SHIELD_MP2") (pintype "power_in"))
      (node (ref "J4") (pin "MP3") (pinfunction "SHIELD_MP3") (pintype "power_in"))
      (node (ref "J4") (pin "MP4") (pinfunction "SHIELD_MP4") (pintype "power_in"))
      (node (ref "P1") (pin "3") (pinfunction "3_3") (pintype "passive"))
      (node (ref "P1") (pin "MP1") (pinfunction "MP1_MP1") (pintype "passive"))
      (node (ref "P1") (pin "MP2") (pinfunction "MP2_MP2") (pintype "passive"))
      (node (ref "R11") (pin "1") (pinfunction "1_1") (pintype "passive"))
      (node (ref "R14") (pin "1") (pinfunction "1_1") (pintype "passive"))
      (node (ref "R26") (pin "1") (pinfunction "1_1") (pintype "passive"))
      (node (ref "S1") (pin "3") (pinfunction "NO_1_3") (pintype "passive"))
      (node (ref "U1") (pin "3") (pinfunction "VSS_3") (pintype "power_in"))
      (node (ref "U1") (pin "5") (pinfunction "SDO_5") (pintype "bidirectional"))
      (node (ref "U1") (pin "8") (pinfunction "VSS_8") (pintype "power_in"))
      (node (ref "U1") (pin "9") (pinfunction "VSS_9") (pintype "power_in"))
      (node (ref "U2") (pin "6") (pinfunction "GND_6") (pintype "power_in"))
      (node (ref "U2") (pin "7") (pinfunction "GND_7") (pintype "power_in"))
      (node (ref "U4") (pin "2") (pinfunction "GND_2") (pintype "power_in"))
      (node (ref "Y1") (pin "2") (pinfunction "GND_1_2") (pintype "passive"))
      (node (ref "Y1") (pin "4") (pinfunction "GND_2_4") (pintype "passive"))
    )
    (net (code "48") (name "Net-(B1-VCAP)") (class "Default")
      (node (ref "B1") (pin "30") (pinfunction "VCAP_30") (pintype "passive"))
      (node (ref "C10") (pin "2") (pinfunction "2_2") (pintype "passive"))
    )
    (net (code "49") (name "VBAT") (class "Default")
      (node (ref "C16") (pin "2") (pinfunction "2_2") (pintype "passive"))
      (node (ref "D1") (pin "1") (pinfunction "K_1") (pintype "passive"))
      (node (ref "D2") (pin "1") (pinfunction "K_1") (pintype "passive"))
      (node (ref "IC1") (pin "5") (pinfunction "VBUS_5") (pintype "passive"))
      (node (ref "J1") (pin "A4_B9") (pinfunction "VBUS_A_A4_B9") (pintype "power_in"))
      (node (ref "J1") (pin "B4_A9") (pinfunction "VBUS_B_B4_A9") (pintype "power_in"))
      (node (ref "J3") (pin "1") (pinfunction "1_1") (pintype "passive"))
      (node (ref "R21") (pin "1") (pinfunction "1_1") (pintype "passive"))
      (node (ref "U4") (pin "1") (pinfunction "VIN_1") (pintype "power_in"))
      (node (ref "U4") (pin "3") (pinfunction "EN_3") (pintype "input"))
    )
    (net (code "50") (name "unconnected-(B1-PA0-Pad14)") (class "Default")
      (node (ref "B1") (pin "14") (pinfunction "PA0_14") (pintype "passive+no_connect"))
    )
    (net (code "51") (name "unconnected-(B1-PA1-Pad15)") (class "Default")
      (node (ref "B1") (pin "15") (pinfunction "PA1_15") (pintype "passive+no_connect"))
    )
    (net (code "52") (name "unconnected-(B1-PA3-Pad17)") (class "Default")
      (node (ref "B1") (pin "17") (pinfunction "PA3_17") (pintype "passive+no_connect"))
    )
    (net (code "53") (name "unconnected-(B1-PA8-Pad41)") (class "Default")
      (node (ref "B1") (pin "41") (pinfunction "PA8_41") (pintype "passive"))
    )
    (net (code "54") (name "unconnected-(B1-PA9-Pad42)") (class "Default")
      (node (ref "B1") (pin "42") (pinfunction "PA9_42") (pintype "passive+no_connect"))
    )
    (net (code "55") (name "unconnected-(B1-PA10-Pad43)") (class "Default")
      (node (ref "B1") (pin "43") (pinfunction "PA10_43") (pintype "passive+no_connect"))
    )
    (net (code "56") (name "unconnected-(B1-PA15-Pad50)") (class "Default")
      (node (ref "B1") (pin "50") (pinfunction "PA15_50") (pintype "passive+no_connect"))
    )
    (net (code "57") (name "unconnected-(B1-PB0-Pad26)") (class "Default")
      (node (ref "B1") (pin "26") (pinfunction "PB0_26") (pintype "passive+no_connect"))
    )
    (net (code "58") (name "unconnected-(B1-PB1-Pad27)") (class "Default")
      (node (ref "B1") (pin "27") (pinfunction "PB1_27") (pintype "passive+no_connect"))
    )
    (net (code "59") (name "unconnected-(B1-PB2-Pad28)") (class "Default")
      (node (ref "B1") (pin "28") (pinfunction "PB2_28") (pintype "passive+no_connect"))
    )
    (net (code "60") (name "unconnected-(B1-PB4-Pad56)") (class "Default")
      (node (ref "B1") (pin "56") (pinfunction "PB4_56") (pintype "passive+no_connect"))
    )
    (net (code "61") (name "unconnected-(B1-PB5-Pad57)") (class "Default")
      (node (ref "B1") (pin "57") (pinfunction "PB5_57") (pintype "passive+no_connect"))
    )
    (net (code "62") (name "unconnected-(B1-PB6-Pad58)") (class "Default")
      (node (ref "B1") (pin "58") (pinfunction "PB6_58") (pintype "passive+no_connect"))
    )
    (net (code "63") (name "unconnected-(B1-PB7-Pad59)") (class "Default")
      (node (ref "B1") (pin "59") (pinfunction "PB7_59") (pintype "passive+no_connect"))
    )
    (net (code "64") (name "unconnected-(B1-PB8-BARO_SCL-Pad61)") (class "Default")
      (node (ref "B1") (pin "61") (pinfunction "PB8-BARO_SCL_61") (pintype "passive+no_connect"))
    )
    (net (code "65") (name "unconnected-(B1-PB9-BARO_SDA-Pad62)") (class "Default")
      (node (ref "B1") (pin "62") (pinfunction "PB9-BARO_SDA_62") (pintype "passive+no_connect"))
    )
    (net (code "66") (name "unconnected-(B1-PB10-Pad29)") (class "Default")
      (node (ref "B1") (pin "29") (pinfunction "PB10_29") (pintype "passive+no_connect"))
    )
    (net (code "67") (name "unconnected-(B1-PB12-Pad33)") (class "Default")
      (node (ref "B1") (pin "33") (pinfunction "PB12_33") (pintype "passive+no_connect"))
    )
    (net (code "68") (name "unconnected-(B1-PB13-Pad34)") (class "Default")
      (node (ref "B1") (pin "34") (pinfunction "PB13_34") (pintype "passive+no_connect"))
    )
    (net (code "69") (name "unconnected-(B1-PB14-Pad35)") (class "Default")
      (node (ref "B1") (pin "35") (pinfunction "PB14_35") (pintype "passive+no_connect"))
    )
    (net (code "70") (name "unconnected-(B1-PB15-Pad36)") (class "Default")
      (node (ref "B1") (pin "36") (pinfunction "PB15_36") (pintype "passive+no_connect"))
    )
    (net (code "71") (name "unconnected-(B1-PC3-Pad11)") (class "Default")
      (node (ref "B1") (pin "11") (pinfunction "PC3_11") (pintype "passive+no_connect"))
    )
    (net (code "72") (name "unconnected-(B1-PC5-Pad25)") (class "Default")
      (node (ref "B1") (pin "25") (pinfunction "PC5_25") (pintype "passive+no_connect"))
    )
    (net (code "73") (name "unconnected-(B1-PC6-Pad37)") (class "Default")
      (node (ref "B1") (pin "37") (pinfunction "PC6_37") (pintype "passive+no_connect"))
    )
    (net (code "74") (name "unconnected-(B1-PC14-OSC32_IN-Pad3)") (class "Default")
      (node (ref "B1") (pin "3") (pinfunction "PC14-OSC32_IN_3") (pintype "passive+no_connect"))
    )
    (net (code "75") (name "unconnected-(J1-SBU1-PadA8)") (class "Default")
      (node (ref "J1") (pin "A8") (pinfunction "SBU1_A8") (pintype "bidirectional+no_connect"))
    )
    (net (code "76") (name "unconnected-(J1-SBU2-PadB8)") (class "Default")
      (node (ref "J1") (pin "B8") (pinfunction "SBU2_B8") (pintype "bidirectional+no_connect"))
    )
    (net (code "77") (name "unconnected-(S1-COM_2-Pad2)") (class "Default")
      (node (ref "S1") (pin "2") (pinfunction "COM_2_2") (pintype "passive+no_connect"))
    )
    (net (code "78") (name "unconnected-(S1-NO_2-Pad4)") (class "Default")
      (node (ref "S1") (pin "4") (pinfunction "NO_2_4") (pintype "passive+no_connect"))
    )
    (net (code "79") (name "unconnected-(U2-INT2-Pad9)") (class "Default")
      (node (ref "U2") (pin "9") (pinfunction "INT2_9") (pintype "input+no_connect"))
    )
    (net (code "80") (name "unconnected-(U2-NC-Pad10)") (class "Default")
      (node (ref "U2") (pin "10") (pinfunction "NC_10") (pintype "passive+no_connect"))
    )
    (net (code "81") (name "unconnected-(U2-NC-Pad11)") (class "Default")
      (node (ref "U2") (pin "11") (pinfunction "NC_11") (pintype "passive+no_connect"))
    )
    (net (code "82") (name "unconnected-(U4-NC-Pad4)") (class "Default")
      (node (ref "U4") (pin "4") (pinfunction "NC_4") (pintype "passive+no_connect"))
    )
  )
)
